# LED_Matrix.net
KiCad netlist of a schematic drawn in EAGLE
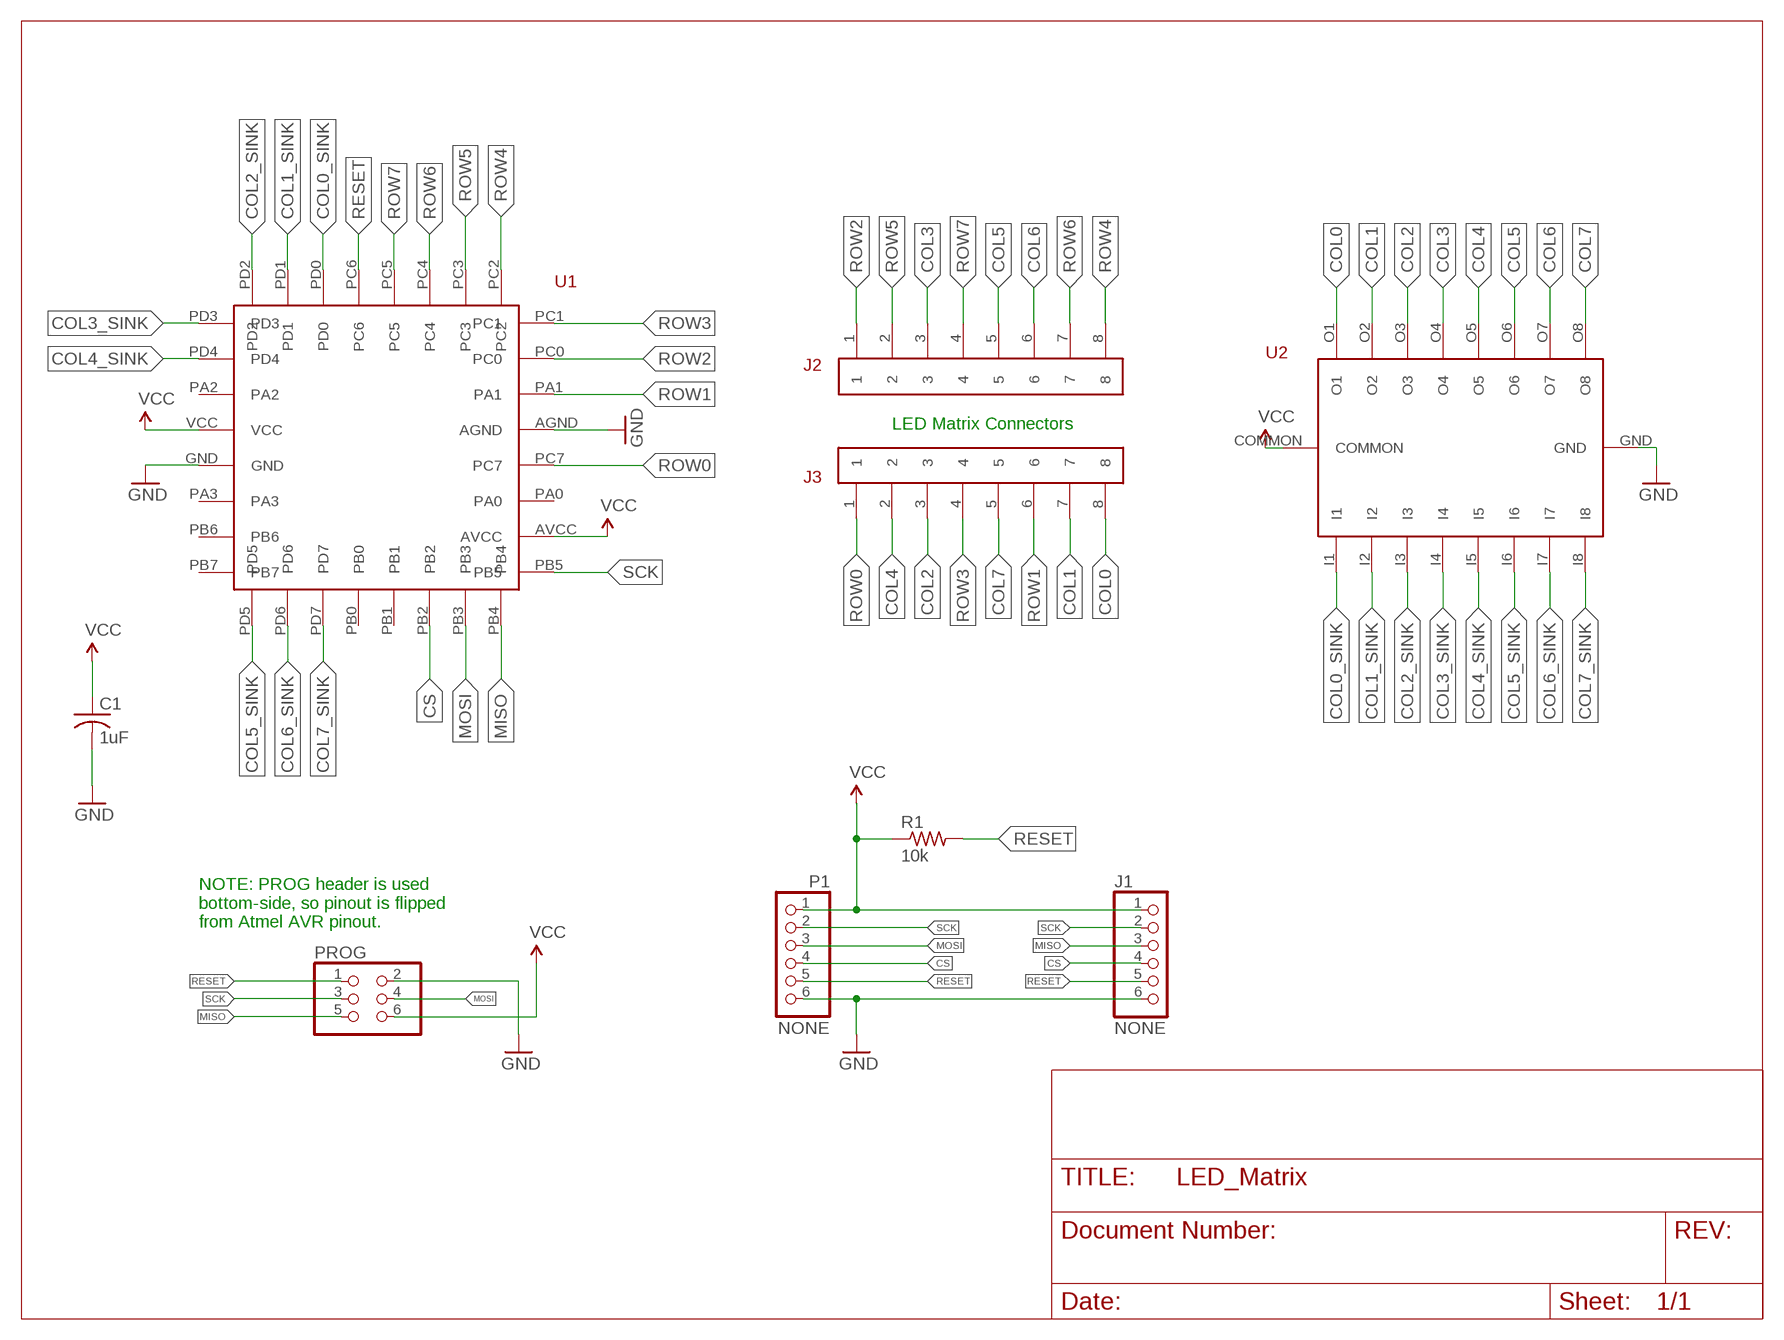
[diagram p0: schematic, sheet 1]

(export (version "E")
  (design (tool "Eeschema 10.0.6"))
  (components
    (comp (ref "C1")
      (value "1uF")
      (footprint "eagle-import:C0603")
      (libsource (lib "eagle-import") (part "C-USC0603"))
    )
    (comp (ref "J1")
      (value "NONE")
      (footprint "eagle-import:1X06")
      (libsource (lib "eagle-import") (part "PINHD-1X6"))
    )
    (comp (ref "J2")
      (value "HEADER-1X8")
      (footprint "eagle-import:HEADER-1X8")
      (libsource (lib "eagle-import") (part "HEADER-1X8"))
    )
    (comp (ref "J3")
      (value "HEADER-1X8")
      (footprint "eagle-import:HEADER-1X8")
      (libsource (lib "eagle-import") (part "HEADER-1X8"))
    )
    (comp (ref "P1")
      (value "NONE")
      (footprint "eagle-import:1X06")
      (libsource (lib "eagle-import") (part "PINHD-1X6"))
    )
    (comp (ref "PROG")
      (value "NONE")
      (footprint "eagle-import:2X03")
      (libsource (lib "eagle-import") (part "PINHD-2X3"))
    )
    (comp (ref "R1")
      (value "10k")
      (footprint "eagle-import:R0603")
      (libsource (lib "eagle-import") (part "R-US_R0603"))
    )
    (comp (ref "U1")
      (value "ATTINY48")
      (footprint "eagle-import:ATTINY48")
      (libsource (lib "eagle-import") (part "ATTINY48"))
    )
    (comp (ref "U2")
      (value "ULN2803AFWG")
      (footprint "eagle-import:ULN2803AFWG")
      (libsource (lib "eagle-import") (part "ULN2803AFWG"))
    )
  )
  (nets
    (net (code "1") (name "COL0") (class "Default")
      (node (ref "J3") (pin "8") (pinfunction "8_8") (pintype "bidirectional"))
      (node (ref "U2") (pin "O1") (pinfunction "O1_O1") (pintype "bidirectional"))
    )
    (net (code "2") (name "COL0_SINK") (class "Default")
      (node (ref "U1") (pin "PD0") (pinfunction "PD0_PD0") (pintype "bidirectional"))
      (node (ref "U2") (pin "I1") (pinfunction "I1_I1") (pintype "bidirectional"))
    )
    (net (code "3") (name "COL1") (class "Default")
      (node (ref "J3") (pin "7") (pinfunction "7_7") (pintype "bidirectional"))
      (node (ref "U2") (pin "O2") (pinfunction "O2_O2") (pintype "bidirectional"))
    )
    (net (code "4") (name "COL1_SINK") (class "Default")
      (node (ref "U1") (pin "PD1") (pinfunction "PD1_PD1") (pintype "bidirectional"))
      (node (ref "U2") (pin "I2") (pinfunction "I2_I2") (pintype "bidirectional"))
    )
    (net (code "5") (name "COL2") (class "Default")
      (node (ref "J3") (pin "3") (pinfunction "3_3") (pintype "bidirectional"))
      (node (ref "U2") (pin "O3") (pinfunction "O3_O3") (pintype "bidirectional"))
    )
    (net (code "6") (name "COL2_SINK") (class "Default")
      (node (ref "U1") (pin "PD2") (pinfunction "PD2_PD2") (pintype "bidirectional"))
      (node (ref "U2") (pin "I3") (pinfunction "I3_I3") (pintype "bidirectional"))
    )
    (net (code "7") (name "COL3") (class "Default")
      (node (ref "J2") (pin "3") (pinfunction "3_3") (pintype "bidirectional"))
      (node (ref "U2") (pin "O4") (pinfunction "O4_O4") (pintype "bidirectional"))
    )
    (net (code "8") (name "COL3_SINK") (class "Default")
      (node (ref "U1") (pin "PD3") (pinfunction "PD3_PD3") (pintype "bidirectional"))
      (node (ref "U2") (pin "I4") (pinfunction "I4_I4") (pintype "bidirectional"))
    )
    (net (code "9") (name "COL4") (class "Default")
      (node (ref "J3") (pin "2") (pinfunction "2_2") (pintype "bidirectional"))
      (node (ref "U2") (pin "O5") (pinfunction "O5_O5") (pintype "bidirectional"))
    )
    (net (code "10") (name "COL4_SINK") (class "Default")
      (node (ref "U1") (pin "PD4") (pinfunction "PD4_PD4") (pintype "bidirectional"))
      (node (ref "U2") (pin "I5") (pinfunction "I5_I5") (pintype "bidirectional"))
    )
    (net (code "11") (name "COL5") (class "Default")
      (node (ref "J2") (pin "5") (pinfunction "5_5") (pintype "bidirectional"))
      (node (ref "U2") (pin "O6") (pinfunction "O6_O6") (pintype "bidirectional"))
    )
    (net (code "12") (name "COL5_SINK") (class "Default")
      (node (ref "U1") (pin "PD5") (pinfunction "PD5_PD5") (pintype "bidirectional"))
      (node (ref "U2") (pin "I6") (pinfunction "I6_I6") (pintype "bidirectional"))
    )
    (net (code "13") (name "COL6") (class "Default")
      (node (ref "J2") (pin "6") (pinfunction "6_6") (pintype "bidirectional"))
      (node (ref "U2") (pin "O7") (pinfunction "O7_O7") (pintype "bidirectional"))
    )
    (net (code "14") (name "COL6_SINK") (class "Default")
      (node (ref "U1") (pin "PD6") (pinfunction "PD6_PD6") (pintype "bidirectional"))
      (node (ref "U2") (pin "I7") (pinfunction "I7_I7") (pintype "bidirectional"))
    )
    (net (code "15") (name "COL7") (class "Default")
      (node (ref "J3") (pin "5") (pinfunction "5_5") (pintype "bidirectional"))
      (node (ref "U2") (pin "O8") (pinfunction "O8_O8") (pintype "bidirectional"))
    )
    (net (code "16") (name "COL7_SINK") (class "Default")
      (node (ref "U1") (pin "PD7") (pinfunction "PD7_PD7") (pintype "bidirectional"))
      (node (ref "U2") (pin "I8") (pinfunction "I8_I8") (pintype "bidirectional"))
    )
    (net (code "17") (name "CS") (class "Default")
      (node (ref "J1") (pin "4") (pinfunction "4_4") (pintype "passive"))
      (node (ref "P1") (pin "4") (pinfunction "4_4") (pintype "passive"))
      (node (ref "U1") (pin "PB2") (pinfunction "PB2_PB2") (pintype "bidirectional"))
    )
    (net (code "18") (name "GND") (class "Default")
      (node (ref "C1") (pin "2") (pinfunction "2_2") (pintype "passive"))
      (node (ref "J1") (pin "6") (pinfunction "6_6") (pintype "passive"))
      (node (ref "P1") (pin "6") (pinfunction "6_6") (pintype "passive"))
      (node (ref "PROG") (pin "2") (pinfunction "2_2") (pintype "passive"))
      (node (ref "U1") (pin "AGND") (pinfunction "AGND_AGND") (pintype "bidirectional"))
      (node (ref "U1") (pin "GND") (pinfunction "GND_GND") (pintype "bidirectional"))
      (node (ref "U2") (pin "GND") (pinfunction "GND_GND") (pintype "bidirectional"))
    )
    (net (code "19") (name "MISO") (class "Default")
      (node (ref "J1") (pin "3") (pinfunction "3_3") (pintype "passive"))
      (node (ref "PROG") (pin "5") (pinfunction "5_5") (pintype "passive"))
      (node (ref "U1") (pin "PB4") (pinfunction "PB4_PB4") (pintype "bidirectional"))
    )
    (net (code "20") (name "MOSI") (class "Default")
      (node (ref "P1") (pin "3") (pinfunction "3_3") (pintype "passive"))
      (node (ref "PROG") (pin "4") (pinfunction "4_4") (pintype "passive"))
      (node (ref "U1") (pin "PB3") (pinfunction "PB3_PB3") (pintype "bidirectional"))
    )
    (net (code "21") (name "RESET") (class "Default")
      (node (ref "J1") (pin "5") (pinfunction "5_5") (pintype "passive"))
      (node (ref "P1") (pin "5") (pinfunction "5_5") (pintype "passive"))
      (node (ref "PROG") (pin "1") (pinfunction "1_1") (pintype "passive"))
      (node (ref "R1") (pin "2") (pinfunction "2_2") (pintype "passive"))
      (node (ref "U1") (pin "PC6") (pinfunction "PC6_PC6") (pintype "bidirectional"))
    )
    (net (code "22") (name "ROW0") (class "Default")
      (node (ref "J3") (pin "1") (pinfunction "1_1") (pintype "bidirectional"))
      (node (ref "U1") (pin "PC7") (pinfunction "PC7_PC7") (pintype "bidirectional"))
    )
    (net (code "23") (name "ROW1") (class "Default")
      (node (ref "J3") (pin "6") (pinfunction "6_6") (pintype "bidirectional"))
      (node (ref "U1") (pin "PA1") (pinfunction "PA1_PA1") (pintype "bidirectional"))
    )
    (net (code "24") (name "ROW2") (class "Default")
      (node (ref "J2") (pin "1") (pinfunction "1_1") (pintype "bidirectional"))
      (node (ref "U1") (pin "PC0") (pinfunction "PC0_PC0") (pintype "bidirectional"))
    )
    (net (code "25") (name "ROW3") (class "Default")
      (node (ref "J3") (pin "4") (pinfunction "4_4") (pintype "bidirectional"))
      (node (ref "U1") (pin "PC1") (pinfunction "PC1_PC1") (pintype "bidirectional"))
    )
    (net (code "26") (name "ROW4") (class "Default")
      (node (ref "J2") (pin "8") (pinfunction "8_8") (pintype "bidirectional"))
      (node (ref "U1") (pin "PC2") (pinfunction "PC2_PC2") (pintype "bidirectional"))
    )
    (net (code "27") (name "ROW5") (class "Default")
      (node (ref "J2") (pin "2") (pinfunction "2_2") (pintype "bidirectional"))
      (node (ref "U1") (pin "PC3") (pinfunction "PC3_PC3") (pintype "bidirectional"))
    )
    (net (code "28") (name "ROW6") (class "Default")
      (node (ref "J2") (pin "7") (pinfunction "7_7") (pintype "bidirectional"))
      (node (ref "U1") (pin "PC4") (pinfunction "PC4_PC4") (pintype "bidirectional"))
    )
    (net (code "29") (name "ROW7") (class "Default")
      (node (ref "J2") (pin "4") (pinfunction "4_4") (pintype "bidirectional"))
      (node (ref "U1") (pin "PC5") (pinfunction "PC5_PC5") (pintype "bidirectional"))
    )
    (net (code "30") (name "SCK") (class "Default")
      (node (ref "J1") (pin "2") (pinfunction "2_2") (pintype "passive"))
      (node (ref "P1") (pin "2") (pinfunction "2_2") (pintype "passive"))
      (node (ref "PROG") (pin "3") (pinfunction "3_3") (pintype "passive"))
      (node (ref "U1") (pin "PB5") (pinfunction "PB5_PB5") (pintype "bidirectional"))
    )
    (net (code "31") (name "VCC") (class "Default")
      (node (ref "C1") (pin "1") (pinfunction "1_1") (pintype "passive"))
      (node (ref "J1") (pin "1") (pinfunction "1_1") (pintype "passive"))
      (node (ref "P1") (pin "1") (pinfunction "1_1") (pintype "passive"))
      (node (ref "PROG") (pin "6") (pinfunction "6_6") (pintype "passive"))
      (node (ref "R1") (pin "1") (pinfunction "1_1") (pintype "passive"))
      (node (ref "U1") (pin "AVCC") (pinfunction "AVCC_AVCC") (pintype "bidirectional"))
      (node (ref "U1") (pin "VCC") (pinfunction "VCC_VCC") (pintype "bidirectional"))
      (node (ref "U2") (pin "COMMON") (pinfunction "COMMON_COMMON") (pintype "bidirectional"))
    )
    (net (code "32") (name "unconnected-(U1-PadPA0)") (class "Default")
      (node (ref "U1") (pin "PA0") (pinfunction "PA0_PA0") (pintype "bidirectional"))
    )
    (net (code "33") (name "unconnected-(U1-PadPA2)") (class "Default")
      (node (ref "U1") (pin "PA2") (pinfunction "PA2_PA2") (pintype "bidirectional"))
    )
    (net (code "34") (name "unconnected-(U1-PadPA3)") (class "Default")
      (node (ref "U1") (pin "PA3") (pinfunction "PA3_PA3") (pintype "bidirectional"))
    )
    (net (code "35") (name "unconnected-(U1-PadPB0)") (class "Default")
      (node (ref "U1") (pin "PB0") (pinfunction "PB0_PB0") (pintype "bidirectional"))
    )
    (net (code "36") (name "unconnected-(U1-PadPB1)") (class "Default")
      (node (ref "U1") (pin "PB1") (pinfunction "PB1_PB1") (pintype "bidirectional"))
    )
    (net (code "37") (name "unconnected-(U1-PadPB6)") (class "Default")
      (node (ref "U1") (pin "PB6") (pinfunction "PB6_PB6") (pintype "bidirectional"))
    )
    (net (code "38") (name "unconnected-(U1-PadPB7)") (class "Default")
      (node (ref "U1") (pin "PB7") (pinfunction "PB7_PB7") (pintype "bidirectional"))
    )
  )
)
